# MCU_Core.net
KiCad netlist of a schematic drawn in Altium Designer
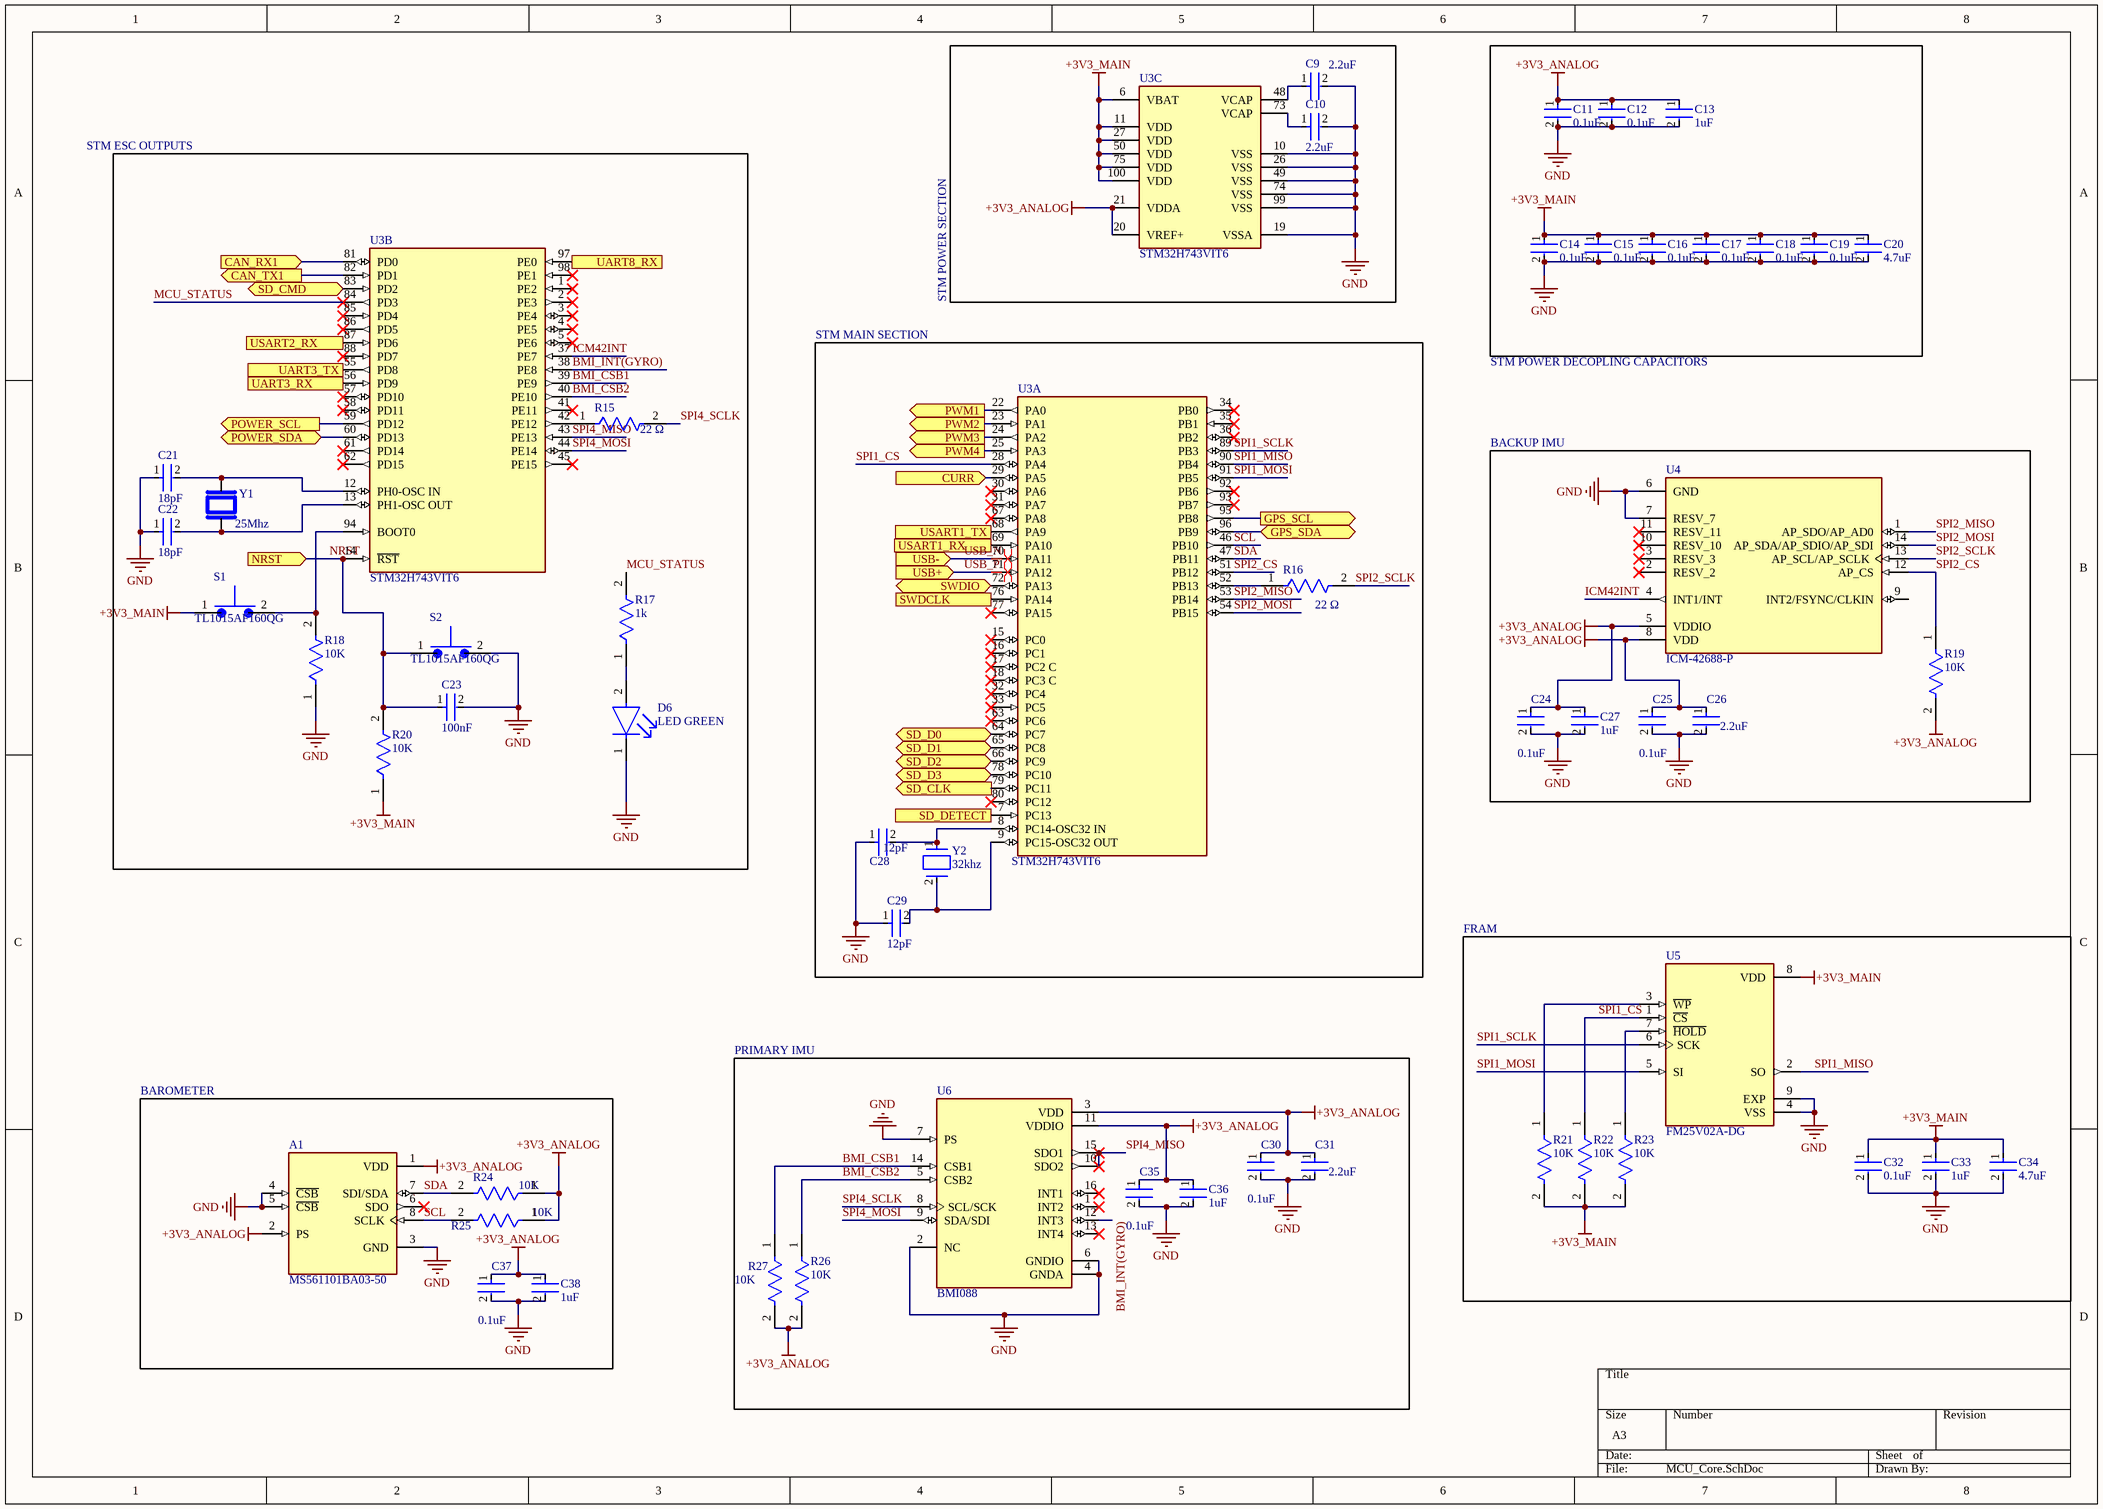
[diagram p0: MCU_Core.SchDoc]

(export (version "E")
  (design (tool "Eeschema 10.0.6"))
  (components
    (comp (ref "A1")
      (value "MS561101BA03-50")
      (footprint "XDCR_MS561101BA03-50")
      (description "Sensor;MS5611-BT M-CAPS 3X5X1MM T&R;Pressure;MS561101BA03-50 ¦ TE Connectivity MS561101BA03-50")
      (fields (field (name "MF") "TE Connectivity"))
      (libsource (lib "MS561101BA03-50") (part "MS561101BA03-50"))
    )
    (comp (ref "C9")
      (value "2.2uF")
      (footprint "FP-GRM155-0_15-IPC_A")
      (description "Chip Multilayer Ceramic Capacitors for General Purpose, 0402, 2.2uF, X7R, 15%, 10%, 10V")
      (libsource (lib "Altium Content Vault") (part "b4654b650e69147ec39a6b967a45e02"))
    )
    (comp (ref "C10")
      (value "2.2uF")
      (footprint "FP-GRM155-0_15-IPC_A")
      (description "Chip Multilayer Ceramic Capacitors for General Purpose, 0402, 2.2uF, X7R, 15%, 10%, 10V")
      (libsource (lib "Altium Content Vault") (part "b4654b650e69147ec39a6b967a45e02"))
    )
    (comp (ref "C11")
      (value "0.1uF")
      (footprint "FP-C0402-BB-MFG")
      (description "CAP CER 0.1UF 10V X7R 0402")
      (fields (field (name "MANUFACTURER") "Kemet") (field (name "TOLERANCE") "0.1"))
      (libsource (lib "Altium Content Vault") (part "b4654b650e69147ec39a6b967a45e02"))
    )
    (comp (ref "C12")
      (value "0.1uF")
      (footprint "FP-C0402-BB-MFG")
      (description "CAP CER 0.1UF 10V X7R 0402")
      (fields (field (name "MANUFACTURER") "Kemet") (field (name "TOLERANCE") "0.1"))
      (libsource (lib "Altium Content Vault") (part "b4654b650e69147ec39a6b967a45e02"))
    )
    (comp (ref "C13")
      (value "1uF")
      (footprint "FP-GRM155-0_05-IPC_B")
      (description "Chip Multilayer Ceramic Capacitors for General Purpose, 0402, 1.0uF, X7R, 15%, 20%, 6.3V")
      (libsource (lib "Altium Content Vault") (part "02cd4be3c70576c341d710602a673aa"))
    )
    (comp (ref "C14")
      (value "0.1uF")
      (footprint "FP-C0402-BB-MFG")
      (description "CAP CER 0.1UF 10V X7R 0402")
      (fields (field (name "MANUFACTURER") "Kemet") (field (name "TOLERANCE") "0.1"))
      (libsource (lib "Altium Content Vault") (part "b4654b650e69147ec39a6b967a45e02"))
    )
    (comp (ref "C15")
      (value "0.1uF")
      (footprint "FP-C0402-BB-MFG")
      (description "CAP CER 0.1UF 10V X7R 0402")
      (fields (field (name "MANUFACTURER") "Kemet") (field (name "TOLERANCE") "0.1"))
      (libsource (lib "Altium Content Vault") (part "b4654b650e69147ec39a6b967a45e02"))
    )
    (comp (ref "C16")
      (value "0.1uF")
      (footprint "FP-C0402-BB-MFG")
      (description "CAP CER 0.1UF 10V X7R 0402")
      (fields (field (name "MANUFACTURER") "Kemet") (field (name "TOLERANCE") "0.1"))
      (libsource (lib "Altium Content Vault") (part "b4654b650e69147ec39a6b967a45e02"))
    )
    (comp (ref "C17")
      (value "0.1uF")
      (footprint "FP-C0402-BB-MFG")
      (description "CAP CER 0.1UF 10V X7R 0402")
      (fields (field (name "MANUFACTURER") "Kemet") (field (name "TOLERANCE") "0.1"))
      (libsource (lib "Altium Content Vault") (part "b4654b650e69147ec39a6b967a45e02"))
    )
    (comp (ref "C18")
      (value "0.1uF")
      (footprint "FP-C0402-BB-MFG")
      (description "CAP CER 0.1UF 10V X7R 0402")
      (fields (field (name "MANUFACTURER") "Kemet") (field (name "TOLERANCE") "0.1"))
      (libsource (lib "Altium Content Vault") (part "b4654b650e69147ec39a6b967a45e02"))
    )
    (comp (ref "C19")
      (value "0.1uF")
      (footprint "FP-C0402-BB-MFG")
      (description "CAP CER 0.1UF 10V X7R 0402")
      (fields (field (name "MANUFACTURER") "Kemet") (field (name "TOLERANCE") "0.1"))
      (libsource (lib "Altium Content Vault") (part "b4654b650e69147ec39a6b967a45e02"))
    )
    (comp (ref "C20")
      (value "4.7uF")
      (footprint "FP-GRT155-0_15-MFG")
      (description "Multi-Layer Ceramic Capacitor 4.7uF 10V X5R ±20% 0402 Paper T/R")
      (libsource (lib "Altium Content Vault") (part "11868f565c42a9108669ba33697ecf6"))
    )
    (comp (ref "C21")
      (value "18pF")
      (footprint "FP-C0402-BB-MFG")
      (description "C0402 18 pF X8R 5.00% 50 V")
      (fields
        (field (name "OCTOPART") "https://octopart.com/c0402c180j5hacauto-kemet-88080534")
        (field (name "MANUFACTURER") "Kemet")
      )
      (libsource (lib "Altium Content Vault") (part "b4654b650e69147ec39a6b967a45e02"))
    )
    (comp (ref "C22")
      (value "18pF")
      (footprint "FP-C0402-BB-MFG")
      (description "C0402 18 pF X8R 5.00% 50 V")
      (fields
        (field (name "OCTOPART") "https://octopart.com/c0402c180j5hacauto-kemet-88080534")
        (field (name "MANUFACTURER") "Kemet")
      )
      (libsource (lib "Altium Content Vault") (part "b4654b650e69147ec39a6b967a45e02"))
    )
    (comp (ref "C23")
      (value "100nF")
      (footprint "FP-C0402-BB-MFG")
      (description "CAP CER 0.1UF 10V X7R 0402")
      (fields (field (name "MANUFACTURER") "Kemet") (field (name "TOLERANCE") "0.1"))
      (libsource (lib "Altium Content Vault") (part "b4654b650e69147ec39a6b967a45e02"))
    )
    (comp (ref "C24")
      (value "0.1uF")
      (footprint "FP-C0402-BB-MFG")
      (description "CAP CER 0.1UF 10V X7R 0402")
      (fields (field (name "MANUFACTURER") "Kemet") (field (name "TOLERANCE") "0.1"))
      (libsource (lib "Altium Content Vault") (part "b4654b650e69147ec39a6b967a45e02"))
    )
    (comp (ref "C25")
      (value "0.1uF")
      (footprint "FP-C0402-BB-MFG")
      (description "CAP CER 0.1UF 10V X7R 0402")
      (fields (field (name "MANUFACTURER") "Kemet") (field (name "TOLERANCE") "0.1"))
      (libsource (lib "Altium Content Vault") (part "b4654b650e69147ec39a6b967a45e02"))
    )
    (comp (ref "C26")
      (value "2.2uF")
      (footprint "FP-GRM155-0_15-IPC_A")
      (description "Chip Multilayer Ceramic Capacitors for General Purpose, 0402, 2.2uF, X7R, 15%, 10%, 10V")
      (libsource (lib "Altium Content Vault") (part "b4654b650e69147ec39a6b967a45e02"))
    )
    (comp (ref "C27")
      (value "1uF")
      (footprint "FP-GRM155-0_05-IPC_B")
      (description "Chip Multilayer Ceramic Capacitors for General Purpose, 0402, 1.0uF, X7R, 15%, 20%, 6.3V")
      (libsource (lib "Altium Content Vault") (part "02cd4be3c70576c341d710602a673aa"))
    )
    (comp (ref "C28")
      (value "12pF")
      (footprint "FP-C0402-BB-MFG")
      (description "C0402 12 pF X8R 5.00% 50 V")
      (fields (field (name "TOLERANCE") "0.05") (field (name "MANUFACTURER") "Kemet"))
      (libsource (lib "Altium Content Vault") (part "b4654b650e69147ec39a6b967a45e02"))
    )
    (comp (ref "C29")
      (value "12pF")
      (footprint "FP-C0402-BB-MFG")
      (description "C0402 12 pF X8R 5.00% 50 V")
      (fields (field (name "TOLERANCE") "0.05") (field (name "MANUFACTURER") "Kemet"))
      (libsource (lib "Altium Content Vault") (part "b4654b650e69147ec39a6b967a45e02"))
    )
    (comp (ref "C30")
      (value "0.1uF")
      (footprint "FP-C0402-BB-MFG")
      (description "CAP CER 0.1UF 10V X7R 0402")
      (fields (field (name "MANUFACTURER") "Kemet") (field (name "TOLERANCE") "0.1"))
      (libsource (lib "Altium Content Vault") (part "b4654b650e69147ec39a6b967a45e02"))
    )
    (comp (ref "C31")
      (value "2.2uF")
      (footprint "FP-GRM155-0_15-IPC_A")
      (description "Chip Multilayer Ceramic Capacitors for General Purpose, 0402, 2.2uF, X7R, 15%, 10%, 10V")
      (libsource (lib "Altium Content Vault") (part "b4654b650e69147ec39a6b967a45e02"))
    )
    (comp (ref "C32")
      (value "0.1uF")
      (footprint "FP-C0402-BB-MFG")
      (description "CAP CER 0.1UF 10V X7R 0402")
      (fields (field (name "MANUFACTURER") "Kemet") (field (name "TOLERANCE") "0.1"))
      (libsource (lib "Altium Content Vault") (part "b4654b650e69147ec39a6b967a45e02"))
    )
    (comp (ref "C33")
      (value "1uF")
      (footprint "FP-GRM155-0_05-IPC_B")
      (description "Chip Multilayer Ceramic Capacitors for General Purpose, 0402, 1.0uF, X7R, 15%, 20%, 6.3V")
      (libsource (lib "Altium Content Vault") (part "02cd4be3c70576c341d710602a673aa"))
    )
    (comp (ref "C34")
      (value "4.7uF")
      (footprint "FP-GRT155-0_15-MFG")
      (description "Multi-Layer Ceramic Capacitor 4.7uF 10V X5R ±20% 0402 Paper T/R")
      (libsource (lib "Altium Content Vault") (part "11868f565c42a9108669ba33697ecf6"))
    )
    (comp (ref "C35")
      (value "0.1uF")
      (footprint "FP-C0402-BB-MFG")
      (description "CAP CER 0.1UF 10V X7R 0402")
      (fields (field (name "MANUFACTURER") "Kemet") (field (name "TOLERANCE") "0.1"))
      (libsource (lib "Altium Content Vault") (part "b4654b650e69147ec39a6b967a45e02"))
    )
    (comp (ref "C36")
      (value "1uF")
      (footprint "FP-GRM155-0_05-IPC_B")
      (description "Chip Multilayer Ceramic Capacitors for General Purpose, 0402, 1.0uF, X7R, 15%, 20%, 6.3V")
      (libsource (lib "Altium Content Vault") (part "02cd4be3c70576c341d710602a673aa"))
    )
    (comp (ref "C37")
      (value "0.1uF")
      (footprint "FP-C0402-BB-MFG")
      (description "CAP CER 0.1UF 10V X7R 0402")
      (fields (field (name "MANUFACTURER") "Kemet") (field (name "TOLERANCE") "0.1"))
      (libsource (lib "Altium Content Vault") (part "b4654b650e69147ec39a6b967a45e02"))
    )
    (comp (ref "C38")
      (value "1uF")
      (footprint "FP-GRM155-0_05-IPC_B")
      (description "Chip Multilayer Ceramic Capacitors for General Purpose, 0402, 1.0uF, X7R, 15%, 20%, 6.3V")
      (libsource (lib "Altium Content Vault") (part "02cd4be3c70576c341d710602a673aa"))
    )
    (comp (ref "D6")
      (value "LED GREEN")
      (footprint "FP-LTST-C171GKT-MFG")
      (description "LED GREEN CLEAR CHIP SMD")
      (libsource (lib "Altium Content Vault") (part "8706943c75ba83719d021d2fdc84c58"))
    )
    (comp (ref "R15")
      (value "22 Ω")
      (footprint "FP-RMCF0402-MFG")
      (description "22Ω ±1% 0.063W 0402 Thick Film Chip Resistor AEC-Q200 compliant")
      (fields (field (name "TOLERANCE") "1%"))
      (libsource (lib "Altium Content Vault") (part "1029c3af85768c4190bb7ad29bc67b5"))
    )
    (comp (ref "R16")
      (value "22 Ω")
      (footprint "FP-RMCF0402-MFG")
      (description "22Ω ±1% 0.063W 0402 Thick Film Chip Resistor AEC-Q200 compliant")
      (fields (field (name "TOLERANCE") "1%"))
      (libsource (lib "Altium Content Vault") (part "1029c3af85768c4190bb7ad29bc67b5"))
    )
    (comp (ref "R17")
      (value "1k")
      (footprint "FP-MCS0402-IPC_A")
      (description "RES SMD 1.2K OHM 1% 1/10W 0402")
      (fields (field (name "TOLERANCE") "0.5%"))
      (libsource (lib "Altium Content Vault") (part "1029c3af85768c4190bb7ad29bc67b5"))
    )
    (comp (ref "R18")
      (value "10K")
      (footprint "FP-MCS0402-MFG")
      (description "RES SMD 1.2K OHM 1% 1/10W 0402")
      (fields (field (name "TOLERANCE") "0.5%"))
      (libsource (lib "Altium Content Vault") (part "1029c3af85768c4190bb7ad29bc67b5"))
    )
    (comp (ref "R19")
      (value "10K")
      (footprint "FP-MCS0402-MFG")
      (description "RES SMD 1.2K OHM 1% 1/10W 0402")
      (fields (field (name "TOLERANCE") "0.5%"))
      (libsource (lib "Altium Content Vault") (part "1029c3af85768c4190bb7ad29bc67b5"))
    )
    (comp (ref "R20")
      (value "10K")
      (footprint "FP-MCS0402-MFG")
      (description "RES SMD 1.2K OHM 1% 1/10W 0402")
      (fields (field (name "TOLERANCE") "0.5%"))
      (libsource (lib "Altium Content Vault") (part "1029c3af85768c4190bb7ad29bc67b5"))
    )
    (comp (ref "R21")
      (value "10K")
      (footprint "FP-MCS0402-MFG")
      (description "RES SMD 1.2K OHM 1% 1/10W 0402")
      (fields (field (name "TOLERANCE") "0.5%"))
      (libsource (lib "Altium Content Vault") (part "1029c3af85768c4190bb7ad29bc67b5"))
    )
    (comp (ref "R22")
      (value "10K")
      (footprint "FP-MCS0402-MFG")
      (description "RES SMD 1.2K OHM 1% 1/10W 0402")
      (fields (field (name "TOLERANCE") "0.5%"))
      (libsource (lib "Altium Content Vault") (part "1029c3af85768c4190bb7ad29bc67b5"))
    )
    (comp (ref "R23")
      (value "10K")
      (footprint "FP-MCS0402-MFG")
      (description "RES SMD 1.2K OHM 1% 1/10W 0402")
      (fields (field (name "TOLERANCE") "0.5%"))
      (libsource (lib "Altium Content Vault") (part "1029c3af85768c4190bb7ad29bc67b5"))
    )
    (comp (ref "R24")
      (value "10K")
      (footprint "FP-MCS0402-MFG")
      (description "RES SMD 1.2K OHM 1% 1/10W 0402")
      (fields (field (name "TOLERANCE") "0.5%"))
      (libsource (lib "Altium Content Vault") (part "1029c3af85768c4190bb7ad29bc67b5"))
    )
    (comp (ref "R25")
      (value "10K")
      (footprint "FP-MCS0402-MFG")
      (description "RES SMD 1.2K OHM 1% 1/10W 0402")
      (fields (field (name "TOLERANCE") "0.5%"))
      (libsource (lib "Altium Content Vault") (part "1029c3af85768c4190bb7ad29bc67b5"))
    )
    (comp (ref "R26")
      (value "10K")
      (footprint "FP-MCS0402-MFG")
      (description "RES SMD 1.2K OHM 1% 1/10W 0402")
      (fields (field (name "TOLERANCE") "0.5%"))
      (libsource (lib "Altium Content Vault") (part "1029c3af85768c4190bb7ad29bc67b5"))
    )
    (comp (ref "R27")
      (value "10K")
      (footprint "FP-MCS0402-MFG")
      (description "RES SMD 1.2K OHM 1% 1/10W 0402")
      (fields (field (name "TOLERANCE") "0.5%"))
      (libsource (lib "Altium Content Vault") (part "1029c3af85768c4190bb7ad29bc67b5"))
    )
    (comp (ref "S1")
      (value "TL1015AF160QG")
      (footprint "SW_TL1015AF160QG")
      (description "Tactile Switch SPST-NO Top Actuated Surface Mount")
      (libsource (lib "3x4mm tactile switch") (part "TL1015AF160QG"))
    )
    (comp (ref "S2")
      (value "TL1015AF160QG")
      (footprint "SW_TL1015AF160QG")
      (description "Tactile Switch SPST-NO Top Actuated Surface Mount")
      (libsource (lib "3x4mm tactile switch") (part "TL1015AF160QG"))
    )
    (comp (ref "U3")
      (value "STM32H743VIT6")
      (footprint "FP-LQFP100-1L-MFG")
      (description "IC MCU 32BIT 2MB FLASH 100LQFP")
      (fields
        (field (name "OCTOPART") "https://octopart.com/stm32h743vit6-stmicroelectronics-76372527")
        (field (name "MANUFACTURER") "STMicroelectronics")
      )
      (libsource (lib "Altium Content Vault") (part "01082ce2885d1d16a22823c45526fe6"))
    )
    (comp (ref "U4")
      (value "ICM-42688-P")
      (footprint "PQFN50P300X250X97-14N")
      (description "Accelerometer, Gyroscope, 6 Axis Sensor Output")
      (libsource (lib "ICM-42688-P") (part "ICM-42688-P"))
    )
    (comp (ref "U5")
      (value "FM25V02A-DG")
      (footprint "SON95P450X400X80-9N")
      (description "FRAM (Ferroelectric RAM) Memory IC 256Kb (32K x 8) SPI 40 MHz 8-DFN (4x4.5)")
      (fields (field (name "MF") "Cypress Semiconductor"))
      (libsource (lib "FM25V02A-DG") (part "FM25V02A-DG"))
    )
    (comp (ref "U6")
      (value "BMI088")
      (footprint "PQFN50P450X300X100-16N")
      (libsource (lib "BMI088") (part "BMI088"))
    )
    (comp (ref "Y1")
      (value "ABM8N-25.0000MHZ-12-B1U-T3")
      (footprint "XTAL_SXT32412BB07-25.000MT")
      (description "25 MHz Â±30ppm Crystal 12pF 50 Ohms 4-SMD, No Lead")
      (fields (field (name "MF") "Suntsu") (field (name "MP") "SXT32412BB07-25.000M"))
      (libsource (lib "SXT32412BB07-25.000MT") (part "SXT32412BB07-25.000MT"))
    )
    (comp (ref "Y2")
      (value "32khz")
      (footprint "FP-ABS07-MFG")
      (description "Crystal 32.768kHz ±20ppm (Tol) 12.5pF FUND 70kΩ 2-Pin CSMD T/R")
      (fields (field (name "TOLERANCE") "20ppm"))
      (libsource (lib "Altium Content Vault") (part "c23a69dc6c9e2f18f2079038eb95dd1"))
    )
  )
  (nets
    (net (code "1") (name "+3V3_ANALOG") (class "Default")
      (node (ref "A1") (pin "1") (pinfunction "VDD_1") (pintype "power_in"))
      (node (ref "A1") (pin "2") (pinfunction "PS_2") (pintype "input"))
      (node (ref "C11") (pin "1") (pinfunction "1_1") (pintype "passive"))
      (node (ref "C12") (pin "1") (pinfunction "1_1") (pintype "passive"))
      (node (ref "C13") (pin "1") (pinfunction "1_1") (pintype "passive"))
      (node (ref "C24") (pin "1") (pinfunction "1_1") (pintype "passive"))
      (node (ref "C25") (pin "1") (pinfunction "1_1") (pintype "passive"))
      (node (ref "C26") (pin "1") (pinfunction "1_1") (pintype "passive"))
      (node (ref "C27") (pin "1") (pinfunction "1_1") (pintype "passive"))
      (node (ref "C30") (pin "1") (pinfunction "1_1") (pintype "passive"))
      (node (ref "C31") (pin "1") (pinfunction "1_1") (pintype "passive"))
      (node (ref "C35") (pin "1") (pinfunction "1_1") (pintype "passive"))
      (node (ref "C36") (pin "1") (pinfunction "1_1") (pintype "passive"))
      (node (ref "C37") (pin "1") (pinfunction "1_1") (pintype "passive"))
      (node (ref "C38") (pin "1") (pinfunction "1_1") (pintype "passive"))
      (node (ref "R19") (pin "2") (pinfunction "2_2") (pintype "passive"))
      (node (ref "R24") (pin "1") (pinfunction "1_1") (pintype "passive"))
      (node (ref "R25") (pin "1") (pinfunction "1_1") (pintype "passive"))
      (node (ref "R26") (pin "2") (pinfunction "2_2") (pintype "passive"))
      (node (ref "R27") (pin "2") (pinfunction "2_2") (pintype "passive"))
      (node (ref "U3") (pin "20") (pinfunction "VREF+_20") (pintype "power_in"))
      (node (ref "U3") (pin "21") (pinfunction "VDDA_21") (pintype "power_in"))
      (node (ref "U4") (pin "5") (pinfunction "VDDIO_5") (pintype "power_in"))
      (node (ref "U4") (pin "8") (pinfunction "VDD_8") (pintype "power_in"))
      (node (ref "U6") (pin "11") (pinfunction "VDDIO_11") (pintype "power_in"))
      (node (ref "U6") (pin "3") (pinfunction "VDD_3") (pintype "power_in"))
    )
    (net (code "2") (name "+3V3_MAIN") (class "Default")
      (node (ref "C14") (pin "1") (pinfunction "1_1") (pintype "passive"))
      (node (ref "C15") (pin "1") (pinfunction "1_1") (pintype "passive"))
      (node (ref "C16") (pin "1") (pinfunction "1_1") (pintype "passive"))
      (node (ref "C17") (pin "1") (pinfunction "1_1") (pintype "passive"))
      (node (ref "C18") (pin "1") (pinfunction "1_1") (pintype "passive"))
      (node (ref "C19") (pin "1") (pinfunction "1_1") (pintype "passive"))
      (node (ref "C20") (pin "1") (pinfunction "1_1") (pintype "passive"))
      (node (ref "C32") (pin "1") (pinfunction "1_1") (pintype "passive"))
      (node (ref "C33") (pin "1") (pinfunction "1_1") (pintype "passive"))
      (node (ref "C34") (pin "1") (pinfunction "1_1") (pintype "passive"))
      (node (ref "R20") (pin "1") (pinfunction "1_1") (pintype "passive"))
      (node (ref "R21") (pin "2") (pinfunction "2_2") (pintype "passive"))
      (node (ref "R22") (pin "2") (pinfunction "2_2") (pintype "passive"))
      (node (ref "R23") (pin "2") (pinfunction "2_2") (pintype "passive"))
      (node (ref "S1") (pin "1") (pinfunction "1_1") (pintype "passive"))
      (node (ref "U3") (pin "100") (pinfunction "VDD_100") (pintype "power_in"))
      (node (ref "U3") (pin "11") (pinfunction "VDD_11") (pintype "power_in"))
      (node (ref "U3") (pin "27") (pinfunction "VDD_27") (pintype "power_in"))
      (node (ref "U3") (pin "50") (pinfunction "VDD_50") (pintype "power_in"))
      (node (ref "U3") (pin "6") (pinfunction "VBAT_6") (pintype "power_in"))
      (node (ref "U3") (pin "75") (pinfunction "VDD_75") (pintype "power_in"))
      (node (ref "U5") (pin "8") (pinfunction "VDD_8") (pintype "power_in"))
    )
    (net (code "3") (name "/BMI_CSB1") (class "Default")
      (node (ref "R27") (pin "1") (pinfunction "1_1") (pintype "passive"))
      (node (ref "U3") (pin "39") (pinfunction "PE9_39") (pintype "output"))
      (node (ref "U6") (pin "14") (pinfunction "CSB1_14") (pintype "input"))
    )
    (net (code "4") (name "/BMI_CSB2") (class "Default")
      (node (ref "R26") (pin "1") (pinfunction "1_1") (pintype "passive"))
      (node (ref "U3") (pin "40") (pinfunction "PE10_40") (pintype "output"))
      (node (ref "U6") (pin "5") (pinfunction "CSB2_5") (pintype "input"))
    )
    (net (code "5") (name "/BMI_INT(GYRO)") (class "Default")
      (node (ref "U3") (pin "38") (pinfunction "PE8_38") (pintype "input"))
      (node (ref "U6") (pin "12") (pinfunction "INT3_12") (pintype "bidirectional"))
    )
    (net (code "6") (name "/CAN_RX1") (class "Default")
      (node (ref "U3") (pin "81") (pinfunction "PD0_81") (pintype "bidirectional"))
    )
    (net (code "7") (name "/CAN_TX1") (class "Default")
      (node (ref "U3") (pin "82") (pinfunction "PD1_82") (pintype "input"))
    )
    (net (code "8") (name "/CURR") (class "Default")
      (node (ref "U3") (pin "29") (pinfunction "PA5_29") (pintype "bidirectional"))
    )
    (net (code "9") (name "/GPS_SCL") (class "Default")
      (node (ref "U3") (pin "95") (pinfunction "PB8_95") (pintype "bidirectional"))
    )
    (net (code "10") (name "/GPS_SDA") (class "Default")
      (node (ref "U3") (pin "96") (pinfunction "PB9_96") (pintype "bidirectional"))
    )
    (net (code "11") (name "/ICM42INT") (class "Default")
      (node (ref "U3") (pin "37") (pinfunction "PE7_37") (pintype "input"))
      (node (ref "U4") (pin "4") (pinfunction "INT1/INT_4") (pintype "output"))
    )
    (net (code "12") (name "/MCU_STATUS") (class "Default")
      (node (ref "R17") (pin "2") (pinfunction "2_2") (pintype "passive"))
      (node (ref "U3") (pin "84") (pinfunction "PD3_84") (pintype "output"))
    )
    (net (code "13") (name "/NRST") (class "Default")
      (node (ref "C23") (pin "1") (pinfunction "1_1") (pintype "passive"))
      (node (ref "R20") (pin "2") (pinfunction "2_2") (pintype "passive"))
      (node (ref "S2") (pin "1") (pinfunction "1_1") (pintype "passive"))
      (node (ref "U3") (pin "14") (pinfunction "~{RST}_14") (pintype "input"))
    )
    (net (code "14") (name "/POWER_SCL") (class "Default")
      (node (ref "U3") (pin "59") (pinfunction "PD12_59") (pintype "output"))
    )
    (net (code "15") (name "/POWER_SDA") (class "Default")
      (node (ref "U3") (pin "60") (pinfunction "PD13_60") (pintype "bidirectional"))
    )
    (net (code "16") (name "/PWM1") (class "Default")
      (node (ref "U3") (pin "22") (pinfunction "PA0_22") (pintype "bidirectional"))
    )
    (net (code "17") (name "/PWM2") (class "Default")
      (node (ref "U3") (pin "23") (pinfunction "PA1_23") (pintype "bidirectional"))
    )
    (net (code "18") (name "/PWM3") (class "Default")
      (node (ref "U3") (pin "24") (pinfunction "PA2_24") (pintype "bidirectional"))
    )
    (net (code "19") (name "/PWM4") (class "Default")
      (node (ref "U3") (pin "25") (pinfunction "PA3_25") (pintype "bidirectional"))
    )
    (net (code "20") (name "/SCL") (class "Default")
      (node (ref "A1") (pin "8") (pinfunction "SCLK_8") (pintype "input"))
      (node (ref "R25") (pin "2") (pinfunction "2_2") (pintype "passive"))
      (node (ref "U3") (pin "46") (pinfunction "PB10_46") (pintype "bidirectional"))
    )
    (net (code "21") (name "/SDA") (class "Default")
      (node (ref "A1") (pin "7") (pinfunction "SDI/SDA_7") (pintype "bidirectional"))
      (node (ref "R24") (pin "2") (pinfunction "2_2") (pintype "passive"))
      (node (ref "U3") (pin "47") (pinfunction "PB11_47") (pintype "bidirectional"))
    )
    (net (code "22") (name "/SD_CLK") (class "Default")
      (node (ref "U3") (pin "79") (pinfunction "PC11_79") (pintype "bidirectional"))
    )
    (net (code "23") (name "/SD_CMD") (class "Default")
      (node (ref "U3") (pin "83") (pinfunction "PD2_83") (pintype "input"))
    )
    (net (code "24") (name "/SD_D0") (class "Default")
      (node (ref "U3") (pin "64") (pinfunction "PC7_64") (pintype "bidirectional"))
    )
    (net (code "25") (name "/SD_D1") (class "Default")
      (node (ref "U3") (pin "65") (pinfunction "PC8_65") (pintype "bidirectional"))
    )
    (net (code "26") (name "/SD_D2") (class "Default")
      (node (ref "U3") (pin "66") (pinfunction "PC9_66") (pintype "bidirectional"))
    )
    (net (code "27") (name "/SD_D3") (class "Default")
      (node (ref "U3") (pin "78") (pinfunction "PC10_78") (pintype "bidirectional"))
    )
    (net (code "28") (name "/SD_DETECT") (class "Default")
      (node (ref "U3") (pin "7") (pinfunction "PC13_7") (pintype "bidirectional"))
    )
    (net (code "29") (name "/SPI1_CS") (class "Default")
      (node (ref "R22") (pin "1") (pinfunction "1_1") (pintype "passive"))
      (node (ref "U3") (pin "28") (pinfunction "PA4_28") (pintype "bidirectional"))
      (node (ref "U5") (pin "1") (pinfunction "~{CS}_1") (pintype "input"))
    )
    (net (code "30") (name "/SPI1_MISO") (class "Default")
      (node (ref "U3") (pin "90") (pinfunction "PB4_90") (pintype "bidirectional"))
      (node (ref "U5") (pin "2") (pinfunction "SO_2") (pintype "output"))
    )
    (net (code "31") (name "/SPI1_MOSI") (class "Default")
      (node (ref "U3") (pin "91") (pinfunction "PB5_91") (pintype "bidirectional"))
      (node (ref "U5") (pin "5") (pinfunction "SI_5") (pintype "input"))
    )
    (net (code "32") (name "/SPI1_SCLK") (class "Default")
      (node (ref "U3") (pin "89") (pinfunction "PB3_89") (pintype "bidirectional"))
      (node (ref "U5") (pin "6") (pinfunction "SCK_6") (pintype "input"))
    )
    (net (code "33") (name "/SPI2_CS") (class "Default")
      (node (ref "R19") (pin "1") (pinfunction "1_1") (pintype "passive"))
      (node (ref "U3") (pin "51") (pinfunction "PB12_51") (pintype "bidirectional"))
      (node (ref "U4") (pin "12") (pinfunction "AP_CS_12") (pintype "input"))
    )
    (net (code "34") (name "/SPI2_MISO") (class "Default")
      (node (ref "U3") (pin "53") (pinfunction "PB14_53") (pintype "bidirectional"))
      (node (ref "U4") (pin "1") (pinfunction "AP_SDO/AP_AD0_1") (pintype "bidirectional"))
    )
    (net (code "35") (name "/SPI2_MOSI") (class "Default")
      (node (ref "U3") (pin "54") (pinfunction "PB15_54") (pintype "bidirectional"))
      (node (ref "U4") (pin "14") (pinfunction "AP_SDA/AP_SDIO/AP_SDI_14") (pintype "bidirectional"))
    )
    (net (code "36") (name "/SPI2_SCLK") (class "Default")
      (node (ref "R16") (pin "2") (pinfunction "2_2") (pintype "passive"))
      (node (ref "U4") (pin "13") (pinfunction "AP_SCL/AP_SCLK_13") (pintype "input"))
    )
    (net (code "37") (name "/SPI4_MISO") (class "Default")
      (node (ref "U3") (pin "43") (pinfunction "PE13_43") (pintype "input"))
      (node (ref "U6") (pin "10") (pinfunction "SDO2_10") (pintype "output"))
      (node (ref "U6") (pin "15") (pinfunction "SDO1_15") (pintype "output"))
    )
    (net (code "38") (name "/SPI4_MOSI") (class "Default")
      (node (ref "U3") (pin "44") (pinfunction "PE14_44") (pintype "bidirectional"))
      (node (ref "U6") (pin "9") (pinfunction "SDA/SDI_9") (pintype "bidirectional"))
    )
    (net (code "39") (name "/SPI4_SCLK") (class "Default")
      (node (ref "R15") (pin "2") (pinfunction "2_2") (pintype "passive"))
      (node (ref "U6") (pin "8") (pinfunction "SCL/SCK_8") (pintype "input"))
    )
    (net (code "40") (name "/SWDCLK") (class "Default")
      (node (ref "U3") (pin "76") (pinfunction "PA14_76") (pintype "bidirectional"))
    )
    (net (code "41") (name "/SWDIO") (class "Default")
      (node (ref "U3") (pin "72") (pinfunction "PA13_72") (pintype "bidirectional"))
    )
    (net (code "42") (name "/UART3_RX") (class "Default")
      (node (ref "U3") (pin "56") (pinfunction "PD9_56") (pintype "input"))
    )
    (net (code "43") (name "/UART3_TX") (class "Default")
      (node (ref "U3") (pin "55") (pinfunction "PD8_55") (pintype "output"))
    )
    (net (code "44") (name "/UART8_RX") (class "Default")
      (node (ref "U3") (pin "97") (pinfunction "PE0_97") (pintype "input"))
    )
    (net (code "45") (name "/USART1_RX") (class "Default")
      (node (ref "U3") (pin "69") (pinfunction "PA10_69") (pintype "bidirectional"))
    )
    (net (code "46") (name "/USART1_TX") (class "Default")
      (node (ref "U3") (pin "68") (pinfunction "PA9_68") (pintype "bidirectional"))
    )
    (net (code "47") (name "/USART2_RX") (class "Default")
      (node (ref "U3") (pin "87") (pinfunction "PD6_87") (pintype "input"))
    )
    (net (code "48") (name "/USB_N") (class "Default")
      (node (ref "U3") (pin "70") (pinfunction "PA11_70") (pintype "bidirectional"))
    )
    (net (code "49") (name "/USB_P") (class "Default")
      (node (ref "U3") (pin "71") (pinfunction "PA12_71") (pintype "bidirectional"))
    )
    (net (code "50") (name "GND") (class "Default")
      (node (ref "A1") (pin "3") (pinfunction "GND_3") (pintype "power_in"))
      (node (ref "A1") (pin "4") (pinfunction "~{CSB}_4") (pintype "input"))
      (node (ref "A1") (pin "5") (pinfunction "~{CSB}_5") (pintype "input"))
      (node (ref "C10") (pin "2") (pinfunction "2_2") (pintype "passive"))
      (node (ref "C11") (pin "2") (pinfunction "2_2") (pintype "passive"))
      (node (ref "C12") (pin "2") (pinfunction "2_2") (pintype "passive"))
      (node (ref "C13") (pin "2") (pinfunction "2_2") (pintype "passive"))
      (node (ref "C14") (pin "2") (pinfunction "2_2") (pintype "passive"))
      (node (ref "C15") (pin "2") (pinfunction "2_2") (pintype "passive"))
      (node (ref "C16") (pin "2") (pinfunction "2_2") (pintype "passive"))
      (node (ref "C17") (pin "2") (pinfunction "2_2") (pintype "passive"))
      (node (ref "C18") (pin "2") (pinfunction "2_2") (pintype "passive"))
      (node (ref "C19") (pin "2") (pinfunction "2_2") (pintype "passive"))
      (node (ref "C20") (pin "2") (pinfunction "2_2") (pintype "passive"))
      (node (ref "C21") (pin "1") (pinfunction "1_1") (pintype "passive"))
      (node (ref "C22") (pin "1") (pinfunction "1_1") (pintype "passive"))
      (node (ref "C23") (pin "2") (pinfunction "2_2") (pintype "passive"))
      (node (ref "C24") (pin "2") (pinfunction "2_2") (pintype "passive"))
      (node (ref "C25") (pin "2") (pinfunction "2_2") (pintype "passive"))
      (node (ref "C26") (pin "2") (pinfunction "2_2") (pintype "passive"))
      (node (ref "C27") (pin "2") (pinfunction "2_2") (pintype "passive"))
      (node (ref "C28") (pin "1") (pinfunction "1_1") (pintype "passive"))
      (node (ref "C29") (pin "1") (pinfunction "1_1") (pintype "passive"))
      (node (ref "C30") (pin "2") (pinfunction "2_2") (pintype "passive"))
      (node (ref "C31") (pin "2") (pinfunction "2_2") (pintype "passive"))
      (node (ref "C32") (pin "2") (pinfunction "2_2") (pintype "passive"))
      (node (ref "C33") (pin "2") (pinfunction "2_2") (pintype "passive"))
      (node (ref "C34") (pin "2") (pinfunction "2_2") (pintype "passive"))
      (node (ref "C35") (pin "2") (pinfunction "2_2") (pintype "passive"))
      (node (ref "C36") (pin "2") (pinfunction "2_2") (pintype "passive"))
      (node (ref "C37") (pin "2") (pinfunction "2_2") (pintype "passive"))
      (node (ref "C38") (pin "2") (pinfunction "2_2") (pintype "passive"))
      (node (ref "C9") (pin "2") (pinfunction "2_2") (pintype "passive"))
      (node (ref "D6") (pin "1") (pinfunction "C_1") (pintype "passive"))
      (node (ref "R18") (pin "1") (pinfunction "1_1") (pintype "passive"))
      (node (ref "S2") (pin "2") (pinfunction "2_2") (pintype "passive"))
      (node (ref "U3") (pin "10") (pinfunction "VSS_10") (pintype "power_in"))
      (node (ref "U3") (pin "19") (pinfunction "VSSA_19") (pintype "power_in"))
      (node (ref "U3") (pin "26") (pinfunction "VSS_26") (pintype "power_in"))
      (node (ref "U3") (pin "49") (pinfunction "VSS_49") (pintype "power_in"))
      (node (ref "U3") (pin "74") (pinfunction "VSS_74") (pintype "power_in"))
      (node (ref "U3") (pin "99") (pinfunction "VSS_99") (pintype "power_in"))
      (node (ref "U4") (pin "6") (pinfunction "GND_6") (pintype "power_in"))
      (node (ref "U4") (pin "7") (pinfunction "RESV_7_7") (pintype "passive"))
      (node (ref "U5") (pin "4") (pinfunction "VSS_4") (pintype "power_in"))
      (node (ref "U5") (pin "9") (pinfunction "EXP_9") (pintype "passive"))
      (node (ref "U6") (pin "2") (pinfunction "NC_2") (pintype "passive"))
      (node (ref "U6") (pin "4") (pinfunction "GNDA_4") (pintype "power_in"))
      (node (ref "U6") (pin "6") (pinfunction "GNDIO_6") (pintype "power_in"))
      (node (ref "U6") (pin "7") (pinfunction "PS_7") (pintype "input"))
    )
    (net (code "51") (name "Net-(C9-Pad1)") (class "Default")
      (node (ref "C9") (pin "1") (pinfunction "1_1") (pintype "passive"))
      (node (ref "U3") (pin "48") (pinfunction "VCAP_48") (pintype "passive"))
    )
    (net (code "52") (name "Net-(C10-Pad1)") (class "Default")
      (node (ref "C10") (pin "1") (pinfunction "1_1") (pintype "passive"))
      (node (ref "U3") (pin "73") (pinfunction "VCAP_73") (pintype "passive"))
    )
    (net (code "53") (name "Net-(D6-A)") (class "Default")
      (node (ref "D6") (pin "2") (pinfunction "A_2") (pintype "passive"))
      (node (ref "R17") (pin "1") (pinfunction "1_1") (pintype "passive"))
    )
    (net (code "54") (name "Net-(U3A-PB13)") (class "Default")
      (node (ref "R16") (pin "1") (pinfunction "1_1") (pintype "passive"))
      (node (ref "U3") (pin "52") (pinfunction "PB13_52") (pintype "bidirectional"))
    )
    (net (code "55") (name "Net-(U3A-PC14-OSC32_IN)") (class "Default")
      (node (ref "C28") (pin "2") (pinfunction "2_2") (pintype "passive"))
      (node (ref "U3") (pin "8") (pinfunction "PC14-OSC32_IN_8") (pintype "bidirectional"))
      (node (ref "Y2") (pin "1") (pinfunction "1_1") (pintype "passive"))
    )
    (net (code "56") (name "Net-(U3A-PC15-OSC32_OUT)") (class "Default")
      (node (ref "C29") (pin "2") (pinfunction "2_2") (pintype "passive"))
      (node (ref "U3") (pin "9") (pinfunction "PC15-OSC32_OUT_9") (pintype "bidirectional"))
      (node (ref "Y2") (pin "2") (pinfunction "2_2") (pintype "passive"))
    )
    (net (code "57") (name "Net-(U3B-BOOT0)") (class "Default")
      (node (ref "R18") (pin "2") (pinfunction "2_2") (pintype "passive"))
      (node (ref "S1") (pin "2") (pinfunction "2_2") (pintype "passive"))
      (node (ref "U3") (pin "94") (pinfunction "BOOT0_94") (pintype "input"))
    )
    (net (code "58") (name "Net-(U3B-PE12)") (class "Default")
      (node (ref "R15") (pin "1") (pinfunction "1_1") (pintype "passive"))
      (node (ref "U3") (pin "42") (pinfunction "PE12_42") (pintype "output"))
    )
    (net (code "59") (name "Net-(U3B-PH0-OSC_IN)") (class "Default")
      (node (ref "C21") (pin "2") (pinfunction "2_2") (pintype "passive"))
      (node (ref "U3") (pin "12") (pinfunction "PH0-OSC_IN_12") (pintype "bidirectional"))
      (node (ref "Y1") (pin "3") (pinfunction "3_3") (pintype "passive"))
    )
    (net (code "60") (name "Net-(U3B-PH1-OSC_OUT)") (class "Default")
      (node (ref "C22") (pin "2") (pinfunction "2_2") (pintype "passive"))
      (node (ref "U3") (pin "13") (pinfunction "PH1-OSC_OUT_13") (pintype "bidirectional"))
      (node (ref "Y1") (pin "1") (pinfunction "1_1") (pintype "passive"))
    )
    (net (code "61") (name "Net-(U5-~{HOLD})") (class "Default")
      (node (ref "R23") (pin "1") (pinfunction "1_1") (pintype "passive"))
      (node (ref "U5") (pin "7") (pinfunction "~{HOLD}_7") (pintype "input"))
    )
    (net (code "62") (name "Net-(U5-~{WP})") (class "Default")
      (node (ref "R21") (pin "1") (pinfunction "1_1") (pintype "passive"))
      (node (ref "U5") (pin "3") (pinfunction "~{WP}_3") (pintype "input"))
    )
    (net (code "63") (name "unconnected-(A1-SDO-Pad6)") (class "Default")
      (node (ref "A1") (pin "6") (pinfunction "SDO_6") (pintype "output+no_connect"))
    )
    (net (code "64") (name "unconnected-(U3A-PA6-Pad30)") (class "Default")
      (node (ref "U3") (pin "30") (pinfunction "PA6_30") (pintype "bidirectional+no_connect"))
    )
    (net (code "65") (name "unconnected-(U3A-PA7-Pad31)") (class "Default")
      (node (ref "U3") (pin "31") (pinfunction "PA7_31") (pintype "bidirectional+no_connect"))
    )
    (net (code "66") (name "unconnected-(U3A-PA8-Pad67)") (class "Default")
      (node (ref "U3") (pin "67") (pinfunction "PA8_67") (pintype "bidirectional+no_connect"))
    )
    (net (code "67") (name "unconnected-(U3A-PA15-Pad77)") (class "Default")
      (node (ref "U3") (pin "77") (pinfunction "PA15_77") (pintype "bidirectional+no_connect"))
    )
    (net (code "68") (name "unconnected-(U3A-PB0-Pad34)") (class "Default")
      (node (ref "U3") (pin "34") (pinfunction "PB0_34") (pintype "bidirectional+no_connect"))
    )
    (net (code "69") (name "unconnected-(U3A-PB1-Pad35)") (class "Default")
      (node (ref "U3") (pin "35") (pinfunction "PB1_35") (pintype "bidirectional+no_connect"))
    )
    (net (code "70") (name "unconnected-(U3A-PB2-Pad36)") (class "Default")
      (node (ref "U3") (pin "36") (pinfunction "PB2_36") (pintype "bidirectional+no_connect"))
    )
    (net (code "71") (name "unconnected-(U3A-PB6-Pad92)") (class "Default")
      (node (ref "U3") (pin "92") (pinfunction "PB6_92") (pintype "bidirectional+no_connect"))
    )
    (net (code "72") (name "unconnected-(U3A-PB7-Pad93)") (class "Default")
      (node (ref "U3") (pin "93") (pinfunction "PB7_93") (pintype "bidirectional+no_connect"))
    )
    (net (code "73") (name "unconnected-(U3A-PC0-Pad15)") (class "Default")
      (node (ref "U3") (pin "15") (pinfunction "PC0_15") (pintype "bidirectional+no_connect"))
    )
    (net (code "74") (name "unconnected-(U3A-PC1-Pad16)") (class "Default")
      (node (ref "U3") (pin "16") (pinfunction "PC1_16") (pintype "bidirectional+no_connect"))
    )
    (net (code "75") (name "unconnected-(U3A-PC2_C-Pad17)") (class "Default")
      (node (ref "U3") (pin "17") (pinfunction "PC2_C_17") (pintype "bidirectional+no_connect"))
    )
    (net (code "76") (name "unconnected-(U3A-PC3_C-Pad18)") (class "Default")
      (node (ref "U3") (pin "18") (pinfunction "PC3_C_18") (pintype "bidirectional+no_connect"))
    )
    (net (code "77") (name "unconnected-(U3A-PC4-Pad32)") (class "Default")
      (node (ref "U3") (pin "32") (pinfunction "PC4_32") (pintype "bidirectional+no_connect"))
    )
    (net (code "78") (name "unconnected-(U3A-PC5-Pad33)") (class "Default")
      (node (ref "U3") (pin "33") (pinfunction "PC5_33") (pintype "bidirectional+no_connect"))
    )
    (net (code "79") (name "unconnected-(U3A-PC6-Pad63)") (class "Default")
      (node (ref "U3") (pin "63") (pinfunction "PC6_63") (pintype "bidirectional+no_connect"))
    )
    (net (code "80") (name "unconnected-(U3A-PC12-Pad80)") (class "Default")
      (node (ref "U3") (pin "80") (pinfunction "PC12_80") (pintype "bidirectional+no_connect"))
    )
    (net (code "81") (name "unconnected-(U3B-PD4-Pad85)") (class "Default")
      (node (ref "U3") (pin "85") (pinfunction "PD4_85") (pintype "input+no_connect"))
    )
    (net (code "82") (name "unconnected-(U3B-PD5-Pad86)") (class "Default")
      (node (ref "U3") (pin "86") (pinfunction "PD5_86") (pintype "output+no_connect"))
    )
    (net (code "83") (name "unconnected-(U3B-PD7-Pad88)") (class "Default")
      (node (ref "U3") (pin "88") (pinfunction "PD7_88") (pintype "input+no_connect"))
    )
    (net (code "84") (name "unconnected-(U3B-PD10-Pad57)") (class "Default")
      (node (ref "U3") (pin "57") (pinfunction "PD10_57") (pintype "bidirectional+no_connect"))
    )
    (net (code "85") (name "unconnected-(U3B-PD11-Pad58)") (class "Default")
      (node (ref "U3") (pin "58") (pinfunction "PD11_58") (pintype "bidirectional+no_connect"))
    )
    (net (code "86") (name "unconnected-(U3B-PD14-Pad61)") (class "Default")
      (node (ref "U3") (pin "61") (pinfunction "PD14_61") (pintype "output+no_connect"))
    )
    (net (code "87") (name "unconnected-(U3B-PD15-Pad62)") (class "Default")
      (node (ref "U3") (pin "62") (pinfunction "PD15_62") (pintype "output+no_connect"))
    )
    (net (code "88") (name "unconnected-(U3B-PE1-Pad98)") (class "Default")
      (node (ref "U3") (pin "98") (pinfunction "PE1_98") (pintype "input+no_connect"))
    )
    (net (code "89") (name "unconnected-(U3B-PE2-Pad1)") (class "Default")
      (node (ref "U3") (pin "1") (pinfunction "PE2_1") (pintype "input+no_connect"))
    )
    (net (code "90") (name "unconnected-(U3B-PE3-Pad2)") (class "Default")
      (node (ref "U3") (pin "2") (pinfunction "PE3_2") (pintype "output+no_connect"))
    )
    (net (code "91") (name "unconnected-(U3B-PE4-Pad3)") (class "Default")
      (node (ref "U3") (pin "3") (pinfunction "PE4_3") (pintype "bidirectional+no_connect"))
    )
    (net (code "92") (name "unconnected-(U3B-PE5-Pad4)") (class "Default")
      (node (ref "U3") (pin "4") (pinfunction "PE5_4") (pintype "bidirectional+no_connect"))
    )
    (net (code "93") (name "unconnected-(U3B-PE6-Pad5)") (class "Default")
      (node (ref "U3") (pin "5") (pinfunction "PE6_5") (pintype "bidirectional+no_connect"))
    )
    (net (code "94") (name "unconnected-(U3B-PE11-Pad41)") (class "Default")
      (node (ref "U3") (pin "41") (pinfunction "PE11_41") (pintype "output+no_connect"))
    )
    (net (code "95") (name "unconnected-(U3B-PE15-Pad45)") (class "Default")
      (node (ref "U3") (pin "45") (pinfunction "PE15_45") (pintype "output+no_connect"))
    )
    (net (code "96") (name "unconnected-(U4-INT2{slash}FSYNC{slash}CLKIN-Pad9)") (class "Default")
      (node (ref "U4") (pin "9") (pinfunction "INT2/FSYNC/CLKIN_9") (pintype "bidirectional"))
    )
    (net (code "97") (name "unconnected-(U4-RESV_2-Pad2)") (class "Default")
      (node (ref "U4") (pin "2") (pinfunction "RESV_2_2") (pintype "passive+no_connect"))
    )
    (net (code "98") (name "unconnected-(U4-RESV_3-Pad3)") (class "Default")
      (node (ref "U4") (pin "3") (pinfunction "RESV_3_3") (pintype "passive+no_connect"))
    )
    (net (code "99") (name "unconnected-(U4-RESV_10-Pad10)") (class "Default")
      (node (ref "U4") (pin "10") (pinfunction "RESV_10_10") (pintype "passive+no_connect"))
    )
    (net (code "100") (name "unconnected-(U4-RESV_11-Pad11)") (class "Default")
      (node (ref "U4") (pin "11") (pinfunction "RESV_11_11") (pintype "passive+no_connect"))
    )
    (net (code "101") (name "unconnected-(U6-INT1-Pad16)") (class "Default")
      (node (ref "U6") (pin "16") (pinfunction "INT1_16") (pintype "bidirectional+no_connect"))
    )
    (net (code "102") (name "unconnected-(U6-INT2-Pad1)") (class "Default")
      (node (ref "U6") (pin "1") (pinfunction "INT2_1") (pintype "bidirectional+no_connect"))
    )
    (net (code "103") (name "unconnected-(U6-INT4-Pad13)") (class "Default")
      (node (ref "U6") (pin "13") (pinfunction "INT4_13") (pintype "bidirectional+no_connect"))
    )
  )
)
